# schematic.net
KiCad netlist of a schematic drawn in EAGLE
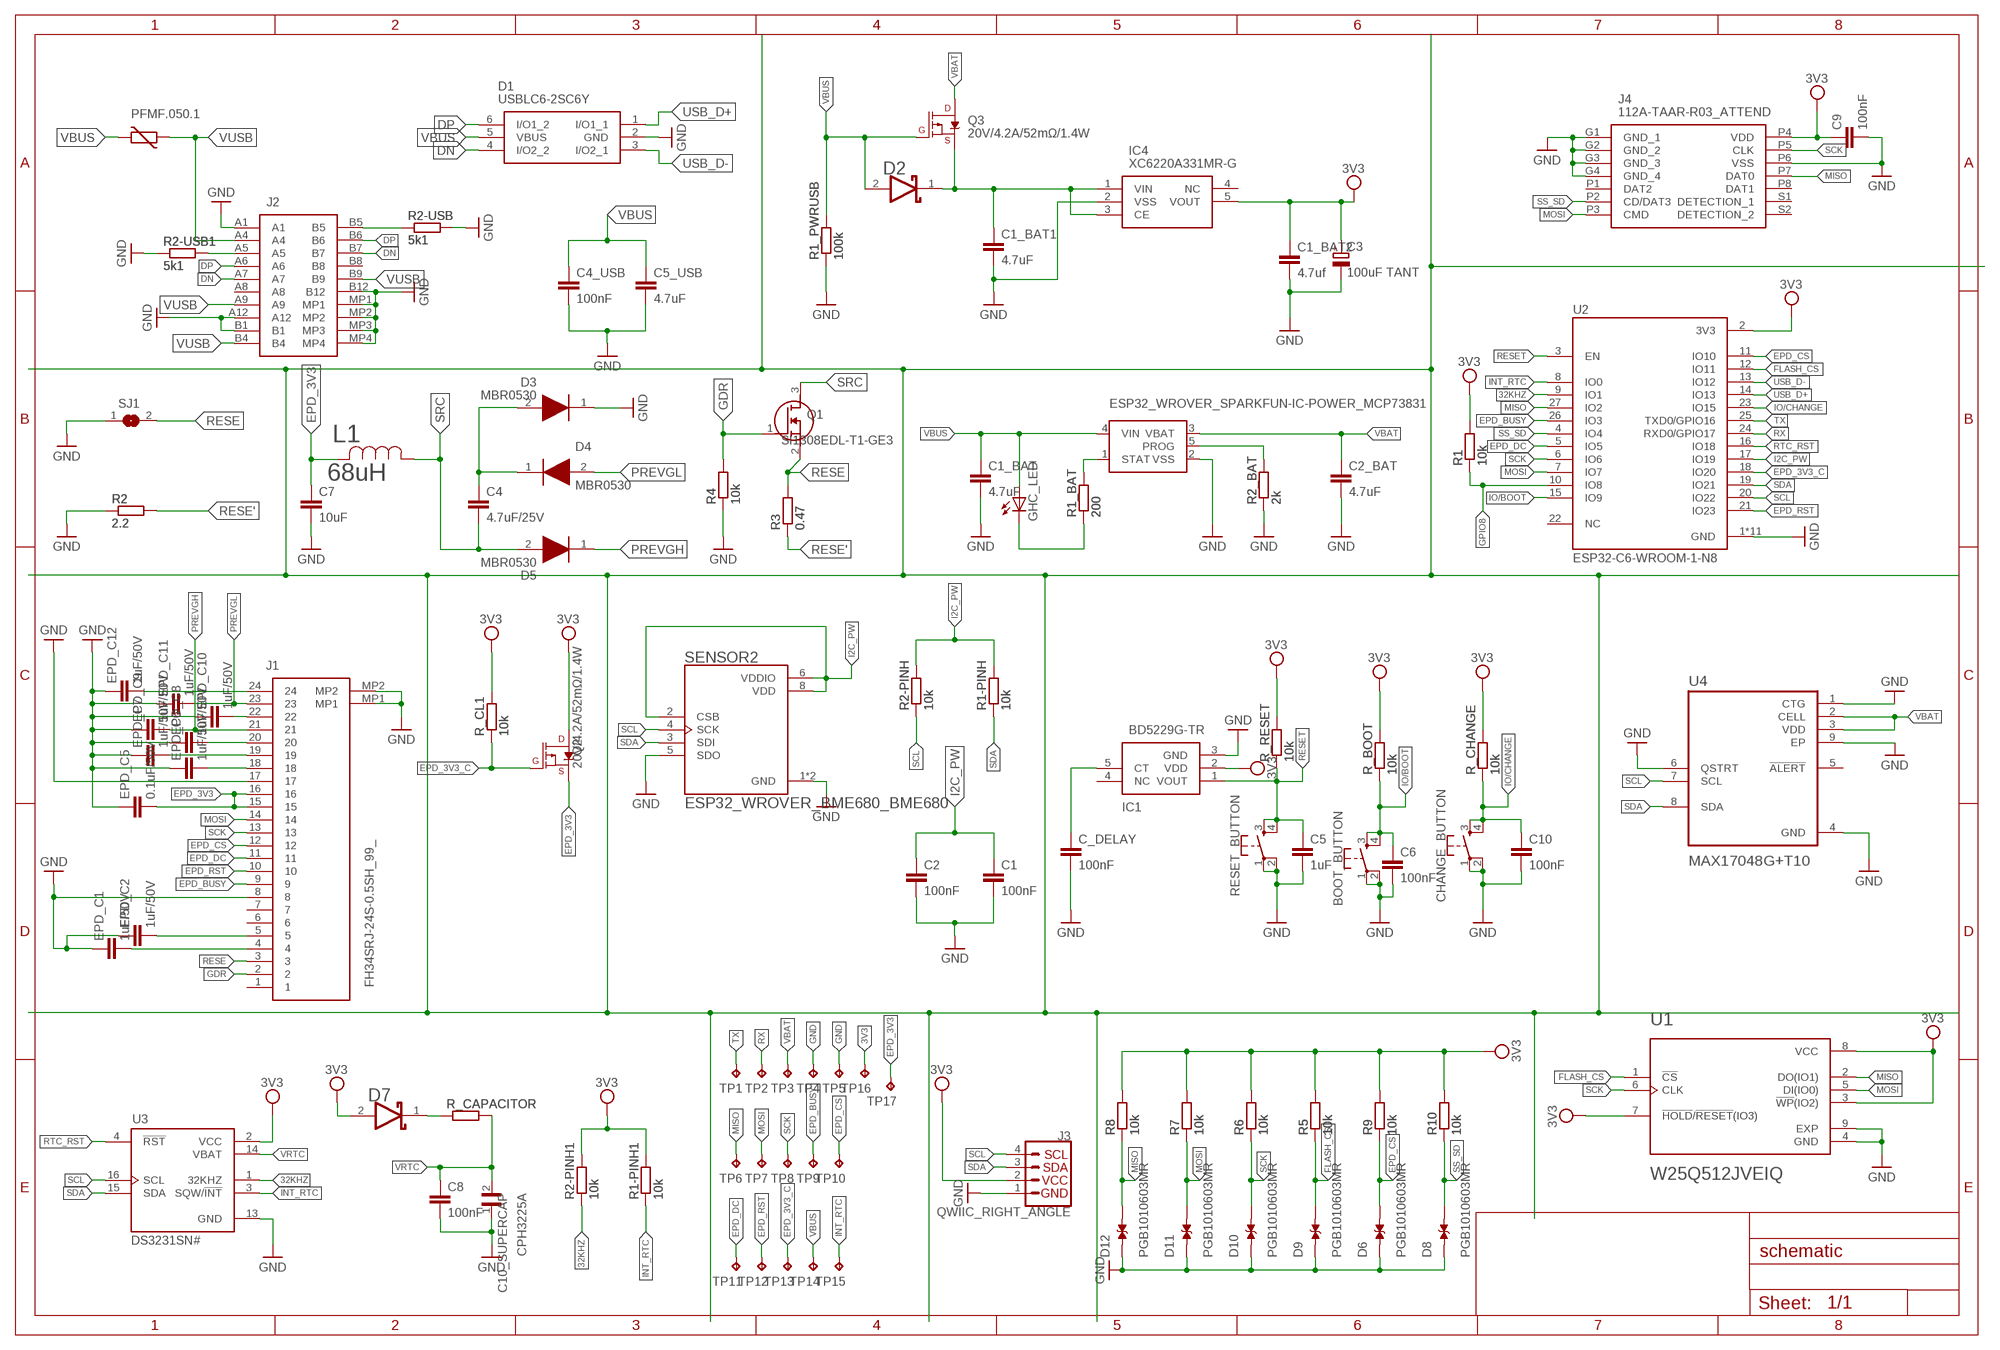
[diagram p0: schematic, sheet 1]

(export (version "E")
  (design (tool "Eeschema 10.0.6"))
  (components
    (comp (ref "BOOT_BUTTON")
      (value "BUTTON_CUSYOMV1")
      (footprint "eagle-import:MYBUTTON")
      (libsource (lib "eagle-import") (part "BUTTON_CUSYOMV1"))
    )
    (comp (ref "C1")
      (value "100nF")
      (footprint "eagle-import:ESP32_WROVER_EAGLE-LTSPICE_C0402")
      (libsource (lib "eagle-import") (part "ESP32_WROVER_EAGLE-LTSPICE_CC0402"))
    )
    (comp (ref "C1_BAT")
      (value "4.7uF")
      (footprint "eagle-import:EAGLE-LTSPICE_C0402")
      (libsource (lib "eagle-import") (part "EAGLE-LTSPICE_CC0402"))
    )
    (comp (ref "C1_BAT1")
      (value "4.7uF")
      (footprint "eagle-import:EAGLE-LTSPICE_C0402")
      (libsource (lib "eagle-import") (part "EAGLE-LTSPICE_CC0402"))
    )
    (comp (ref "C1_BAT2")
      (value "4.7uf")
      (footprint "eagle-import:EAGLE-LTSPICE_C0402")
      (libsource (lib "eagle-import") (part "EAGLE-LTSPICE_CC0402"))
    )
    (comp (ref "C2")
      (value "100nF")
      (footprint "eagle-import:ESP32_WROVER_EAGLE-LTSPICE_C0402")
      (libsource (lib "eagle-import") (part "ESP32_WROVER_EAGLE-LTSPICE_CC0402"))
    )
    (comp (ref "C2_BAT")
      (value "4.7uF")
      (footprint "eagle-import:EAGLE-LTSPICE_C0402")
      (libsource (lib "eagle-import") (part "EAGLE-LTSPICE_CC0402"))
    )
    (comp (ref "C3")
      (value "100uF TANT")
      (footprint "eagle-import:RCL_CT3528")
      (libsource (lib "eagle-import") (part "RCL_CPOL-EUCT3528"))
    )
    (comp (ref "C4")
      (value "4.7uF/25V")
      (footprint "eagle-import:ESP32_WROVER_EAGLE-LTSPICE_C0402")
      (libsource (lib "eagle-import") (part "ESP32_WROVER_EAGLE-LTSPICE_CC0402"))
    )
    (comp (ref "C4_USB")
      (value "100nF")
      (footprint "eagle-import:ESP32_WROVER_EAGLE-LTSPICE_C0402")
      (libsource (lib "eagle-import") (part "ESP32_WROVER_EAGLE-LTSPICE_CC0402"))
    )
    (comp (ref "C5")
      (value "1uF")
      (footprint "eagle-import:ESP32_WROVER_EAGLE-LTSPICE_C0402")
      (libsource (lib "eagle-import") (part "ESP32_WROVER_EAGLE-LTSPICE_CC0402"))
    )
    (comp (ref "C5_USB")
      (value "4.7uF")
      (footprint "eagle-import:ESP32_WROVER_EAGLE-LTSPICE_C0402")
      (libsource (lib "eagle-import") (part "ESP32_WROVER_EAGLE-LTSPICE_CC0402"))
    )
    (comp (ref "C6")
      (value "100nF")
      (footprint "eagle-import:ESP32_WROVER_EAGLE-LTSPICE_C0402")
      (libsource (lib "eagle-import") (part "ESP32_WROVER_EAGLE-LTSPICE_CC0402"))
    )
    (comp (ref "C7")
      (value "10uF")
      (footprint "eagle-import:ESP32_WROVER_EAGLE-LTSPICE_C0402")
      (libsource (lib "eagle-import") (part "ESP32_WROVER_EAGLE-LTSPICE_CC0402"))
    )
    (comp (ref "C8")
      (value "100nF")
      (footprint "eagle-import:ESP32_WROVER_EAGLE-LTSPICE_C0402")
      (libsource (lib "eagle-import") (part "ESP32_WROVER_EAGLE-LTSPICE_CC0402"))
    )
    (comp (ref "C9")
      (value "100nF")
      (footprint "eagle-import:ESP32_WROVER_EAGLE-LTSPICE_C0402")
      (libsource (lib "eagle-import") (part "ESP32_WROVER_EAGLE-LTSPICE_CC0402"))
    )
    (comp (ref "C10")
      (value "100nF")
      (footprint "eagle-import:ESP32_WROVER_EAGLE-LTSPICE_C0402")
      (libsource (lib "eagle-import") (part "ESP32_WROVER_EAGLE-LTSPICE_CC0402"))
    )
    (comp (ref "C10_SUPERCAP")
      (value "CPH3225A")
      (footprint "eagle-import:CAPCP3225X100N")
      (fields (field (name "MF") "Seiko Instruments"))
      (libsource (lib "eagle-import") (part "CPH3225A"))
    )
    (comp (ref "CHANGE_BUTTON")
      (value "BUTTON_CUSYOMV1")
      (footprint "eagle-import:MYBUTTON")
      (libsource (lib "eagle-import") (part "BUTTON_CUSYOMV1"))
    )
    (comp (ref "C_DELAY")
      (value "100nF")
      (footprint "eagle-import:ESP32_WROVER_EAGLE-LTSPICE_C0402")
      (libsource (lib "eagle-import") (part "ESP32_WROVER_EAGLE-LTSPICE_CC0402"))
    )
    (comp (ref "D1")
      (value "USBLC6-2SC6Y")
      (footprint "eagle-import:SOT95P280X145-6N")
      (fields (field (name "MF") "STMicroelectronics"))
      (libsource (lib "eagle-import") (part "USBLC6-2SC6Y"))
    )
    (comp (ref "D2")
      (value "ESP32_WROVER_AVX---SD0805S020S1R0_AVX_SD0805S020S1R0_0_0AVX_SD0805S020S1R0_0_0")
      (footprint "eagle-import:ESP32_WROVER_AVX---SD0805S020S1R0_AVX_SD0805S020S1R0_0")
      (fields
        (field (name "DIGIKEY_PART_NUMBER") "478-7800-1-ND")
        (field (name "MF") "AVX")
        (field (name "MOUSER_PART_NUMBER") "581-SD0805S020S1R0")
      )
      (libsource (lib "eagle-import") (part "ESP32_WROVER_AVX---SD0805S020S1R0_AVX_SD0805S020S1R0_0_0AVX_SD0805S020S1R0_0_0"))
    )
    (comp (ref "D3")
      (value "MBR0530")
      (footprint "eagle-import:SOD3716X135N")
      (fields (field (name "MF") "ON Semiconductor"))
      (libsource (lib "eagle-import") (part "MBR0530"))
    )
    (comp (ref "D4")
      (value "MBR0530")
      (footprint "eagle-import:SOD3716X135N")
      (fields (field (name "MF") "ON Semiconductor"))
      (libsource (lib "eagle-import") (part "MBR0530"))
    )
    (comp (ref "D5")
      (value "MBR0530")
      (footprint "eagle-import:SOD3716X135N")
      (fields (field (name "MF") "ON Semiconductor"))
      (libsource (lib "eagle-import") (part "MBR0530"))
    )
    (comp (ref "D6")
      (value "PGB1010603MR")
      (footprint "eagle-import:DIOC1608X36N")
      (fields (field (name "MF") "Littelfuse Inc."))
      (libsource (lib "eagle-import") (part "PGB1010603MR"))
    )
    (comp (ref "D7")
      (value "ESP32_WROVER_AVX---SD0805S020S1R0_AVX_SD0805S020S1R0_0_0AVX_SD0805S020S1R0_0_0")
      (footprint "eagle-import:ESP32_WROVER_AVX---SD0805S020S1R0_AVX_SD0805S020S1R0_0")
      (fields
        (field (name "DIGIKEY_PART_NUMBER") "478-7800-1-ND")
        (field (name "MF") "AVX")
        (field (name "MOUSER_PART_NUMBER") "581-SD0805S020S1R0")
      )
      (libsource (lib "eagle-import") (part "ESP32_WROVER_AVX---SD0805S020S1R0_AVX_SD0805S020S1R0_0_0AVX_SD0805S020S1R0_0_0"))
    )
    (comp (ref "D8")
      (value "PGB1010603MR")
      (footprint "eagle-import:DIOC1608X36N")
      (fields (field (name "MF") "Littelfuse Inc."))
      (libsource (lib "eagle-import") (part "PGB1010603MR"))
    )
    (comp (ref "D9")
      (value "PGB1010603MR")
      (footprint "eagle-import:DIOC1608X36N")
      (fields (field (name "MF") "Littelfuse Inc."))
      (libsource (lib "eagle-import") (part "PGB1010603MR"))
    )
    (comp (ref "D10")
      (value "PGB1010603MR")
      (footprint "eagle-import:DIOC1608X36N")
      (fields (field (name "MF") "Littelfuse Inc."))
      (libsource (lib "eagle-import") (part "PGB1010603MR"))
    )
    (comp (ref "D11")
      (value "PGB1010603MR")
      (footprint "eagle-import:DIOC1608X36N")
      (fields (field (name "MF") "Littelfuse Inc."))
      (libsource (lib "eagle-import") (part "PGB1010603MR"))
    )
    (comp (ref "D12")
      (value "PGB1010603MR")
      (footprint "eagle-import:DIOC1608X36N")
      (fields (field (name "MF") "Littelfuse Inc."))
      (libsource (lib "eagle-import") (part "PGB1010603MR"))
    )
    (comp (ref "EPD_C1")
      (value "1uF/50V")
      (footprint "eagle-import:ESP32_WROVER_EAGLE-LTSPICE_C0402")
      (libsource (lib "eagle-import") (part "ESP32_WROVER_EAGLE-LTSPICE_CC0402"))
    )
    (comp (ref "EPD_C2")
      (value "1uF/50V")
      (footprint "eagle-import:ESP32_WROVER_EAGLE-LTSPICE_C0402")
      (libsource (lib "eagle-import") (part "ESP32_WROVER_EAGLE-LTSPICE_CC0402"))
    )
    (comp (ref "EPD_C5")
      (value "0.1uF/50V")
      (footprint "eagle-import:ESP32_WROVER_EAGLE-LTSPICE_C0402")
      (libsource (lib "eagle-import") (part "ESP32_WROVER_EAGLE-LTSPICE_CC0402"))
    )
    (comp (ref "EPD_C6")
      (value "1uF/50V")
      (footprint "eagle-import:ESP32_WROVER_EAGLE-LTSPICE_C0402")
      (libsource (lib "eagle-import") (part "ESP32_WROVER_EAGLE-LTSPICE_CC0402"))
    )
    (comp (ref "EPD_C7")
      (value "1uF/50V")
      (footprint "eagle-import:ESP32_WROVER_EAGLE-LTSPICE_C0402")
      (libsource (lib "eagle-import") (part "ESP32_WROVER_EAGLE-LTSPICE_CC0402"))
    )
    (comp (ref "EPD_C8")
      (value "1uF/50V")
      (footprint "eagle-import:ESP32_WROVER_EAGLE-LTSPICE_C0402")
      (libsource (lib "eagle-import") (part "ESP32_WROVER_EAGLE-LTSPICE_CC0402"))
    )
    (comp (ref "EPD_C9")
      (value "1uF/50V")
      (footprint "eagle-import:ESP32_WROVER_EAGLE-LTSPICE_C0402")
      (libsource (lib "eagle-import") (part "ESP32_WROVER_EAGLE-LTSPICE_CC0402"))
    )
    (comp (ref "EPD_C10")
      (value "1uF/50V")
      (footprint "eagle-import:ESP32_WROVER_EAGLE-LTSPICE_C0402")
      (libsource (lib "eagle-import") (part "ESP32_WROVER_EAGLE-LTSPICE_CC0402"))
    )
    (comp (ref "EPD_C11")
      (value "1uF/50V")
      (footprint "eagle-import:ESP32_WROVER_EAGLE-LTSPICE_C0402")
      (libsource (lib "eagle-import") (part "ESP32_WROVER_EAGLE-LTSPICE_CC0402"))
    )
    (comp (ref "EPD_C12")
      (value "1uF/50V")
      (footprint "eagle-import:ESP32_WROVER_EAGLE-LTSPICE_C0402")
      (libsource (lib "eagle-import") (part "ESP32_WROVER_EAGLE-LTSPICE_CC0402"))
    )
    (comp (ref "GHC_LED")
      (value "ADAFRUIT_LEDCHIP-LED0603")
      (footprint "eagle-import:ADAFRUIT_CHIP-LED0603")
      (libsource (lib "eagle-import") (part "ADAFRUIT_LEDCHIP-LED0603"))
    )
    (comp (ref "IC1")
      (value "BD5229G-TR")
      (footprint "eagle-import:SOT95P280X125-5N")
      (fields (field (name "MOUSER_PART_NUMBER") "755-BD5229G-TR"))
      (libsource (lib "eagle-import") (part "BD5229G-TR"))
    )
    (comp (ref "IC4")
      (value "XC6220A331MR-G")
      (footprint "eagle-import:SOT95P280X120-5N")
      (fields (field (name "MOUSER_PART_NUMBER") "865-XC6220A331MR-G"))
      (libsource (lib "eagle-import") (part "XC6220A331MR-G"))
    )
    (comp (ref "J1")
      (value "FH34SRJ-24S-0.5SH_99_")
      (footprint "eagle-import:FH34SRJ24S05SH99")
      (fields
        (field (name "MANUFACTURER_PART_NUMBER") "FH34SRJ-24S-0.5SH(99)")
        (field (name "MOUSER_PART_NUMBER") "798-FH34SRJ24S05SH99")
      )
      (libsource (lib "eagle-import") (part "FH34SRJ-24S-0.5SH_99_"))
    )
    (comp (ref "J2")
      (value "SAMACSYS_PARTS_USB4110-GF-A")
      (footprint "eagle-import:SAMACSYS_PARTS_USB4110GFA")
      (fields
        (field (name "MANUFACTURER_PART_NUMBER") "USB4110-GF-A")
        (field (name "MOUSER_PART_NUMBER") "640-USB4110-GF-A")
      )
      (libsource (lib "eagle-import") (part "SAMACSYS_PARTS_USB4110-GF-A"))
    )
    (comp (ref "J3")
      (value "QWIIC_RIGHT_ANGLE")
      (footprint "eagle-import:JST04_1MM_RA")
      (libsource (lib "eagle-import") (part "QWIIC_CONNECTORJS-1MM"))
    )
    (comp (ref "J4")
      (value "112A-TAAR-R03_ATTEND")
      (footprint "eagle-import:112ATAARR03ATTEND")
      (fields (field (name "MANUFACTURER_PART_NUMBER") "112A-TAAR-R03 ATTEND"))
      (libsource (lib "eagle-import") (part "112A-TAAR-R03_ATTEND"))
    )
    (comp (ref "L1")
      (value "68uH")
      (footprint "eagle-import:IND_4828-WE-TPC_WRE")
      (fields
        (field (name "MANUFACTURER_PART_NUMBER") "744043680")
        (field (name "COPYRIGHT") "Copyright (C) 2024 Ultra Librarian. All rights reserved.")
      )
      (libsource (lib "eagle-import") (part "744043680IND_4828-WE-TPC_WRE"))
    )
    (comp (ref "PFMF.050.1")
      (value "ESP32C6_VARISTORCN1812")
      (footprint "eagle-import:ESP32C6_VARISTOR_CT_CN1812")
      (libsource (lib "eagle-import") (part "ESP32C6_VARISTORCN1812"))
    )
    (comp (ref "Q1")
      (value "SI1308EDL-T1-GE3")
      (footprint "eagle-import:SOT65P210X110-3N")
      (fields (field (name "MF") "Vishay Siliconix"))
      (libsource (lib "eagle-import") (part "SI1308EDL-T1-GE3"))
    )
    (comp (ref "Q2")
      (value "20V/4.2A/52mΩ/1.4W")
      (footprint "eagle-import:ESP32_WROVER_SPARKFUN-DISCRETESEMI_SOT23-3")
      (libsource (lib "eagle-import") (part "ESP32_WROVER_SPARKFUN-DISCRETESEMI_MOSFET_PCH-DMG2305UX-7"))
    )
    (comp (ref "Q3")
      (value "20V/4.2A/52mΩ/1.4W")
      (footprint "eagle-import:ESP32_WROVER_SPARKFUN-DISCRETESEMI_SOT23-3")
      (libsource (lib "eagle-import") (part "ESP32_WROVER_SPARKFUN-DISCRETESEMI_MOSFET_PCH-DMG2305UX-7"))
    )
    (comp (ref "R1")
      (value "10k")
      (footprint "eagle-import:ESP32_WROVER_EAGLE-LTSPICE_R0402")
      (libsource (lib "eagle-import") (part "ESP32_WROVER_EAGLE-LTSPICE_RR0402"))
    )
    (comp (ref "R1-PINH")
      (value "10k")
      (footprint "eagle-import:ESP32_WROVER_EAGLE-LTSPICE_R0402")
      (libsource (lib "eagle-import") (part "ESP32_WROVER_EAGLE-LTSPICE_RR0402"))
    )
    (comp (ref "R1-PINH1")
      (value "10k")
      (footprint "eagle-import:ESP32_WROVER_EAGLE-LTSPICE_R0402")
      (libsource (lib "eagle-import") (part "ESP32_WROVER_EAGLE-LTSPICE_RR0402"))
    )
    (comp (ref "R1_BAT")
      (value "200")
      (footprint "eagle-import:ESP32_WROVER_EAGLE-LTSPICE_R0402")
      (libsource (lib "eagle-import") (part "ESP32_WROVER_EAGLE-LTSPICE_RR0402"))
    )
    (comp (ref "R1_PWRUSB")
      (value "100k")
      (footprint "eagle-import:ESP32_WROVER_EAGLE-LTSPICE_R0402")
      (libsource (lib "eagle-import") (part "ESP32_WROVER_EAGLE-LTSPICE_RR0402"))
    )
    (comp (ref "R2")
      (value "2.2")
      (footprint "eagle-import:ESP32_WROVER_EAGLE-LTSPICE_R0402")
      (libsource (lib "eagle-import") (part "ESP32_WROVER_EAGLE-LTSPICE_RR0402"))
    )
    (comp (ref "R2-PINH")
      (value "10k")
      (footprint "eagle-import:ESP32_WROVER_EAGLE-LTSPICE_R0402")
      (libsource (lib "eagle-import") (part "ESP32_WROVER_EAGLE-LTSPICE_RR0402"))
    )
    (comp (ref "R2-PINH1")
      (value "10k")
      (footprint "eagle-import:ESP32_WROVER_EAGLE-LTSPICE_R0402")
      (libsource (lib "eagle-import") (part "ESP32_WROVER_EAGLE-LTSPICE_RR0402"))
    )
    (comp (ref "R2-USB")
      (value "5k1")
      (footprint "eagle-import:ESP32_WROVER_EAGLE-LTSPICE_R0402")
      (libsource (lib "eagle-import") (part "ESP32_WROVER_EAGLE-LTSPICE_RR0402"))
    )
    (comp (ref "R2-USB1")
      (value "5k1")
      (footprint "eagle-import:ESP32_WROVER_EAGLE-LTSPICE_R0402")
      (libsource (lib "eagle-import") (part "ESP32_WROVER_EAGLE-LTSPICE_RR0402"))
    )
    (comp (ref "R2_BAT")
      (value "2k")
      (footprint "eagle-import:ESP32_WROVER_EAGLE-LTSPICE_R0402")
      (libsource (lib "eagle-import") (part "ESP32_WROVER_EAGLE-LTSPICE_RR0402"))
    )
    (comp (ref "R3")
      (value "0.47")
      (footprint "eagle-import:ESP32_WROVER_EAGLE-LTSPICE_R0402")
      (libsource (lib "eagle-import") (part "ESP32_WROVER_EAGLE-LTSPICE_RR0402"))
    )
    (comp (ref "R4")
      (value "10k")
      (footprint "eagle-import:ESP32_WROVER_EAGLE-LTSPICE_R0402")
      (libsource (lib "eagle-import") (part "ESP32_WROVER_EAGLE-LTSPICE_RR0402"))
    )
    (comp (ref "R5")
      (value "10k")
      (footprint "eagle-import:ESP32_WROVER_EAGLE-LTSPICE_R0402")
      (libsource (lib "eagle-import") (part "ESP32_WROVER_EAGLE-LTSPICE_RR0402"))
    )
    (comp (ref "R6")
      (value "10k")
      (footprint "eagle-import:ESP32_WROVER_EAGLE-LTSPICE_R0402")
      (libsource (lib "eagle-import") (part "ESP32_WROVER_EAGLE-LTSPICE_RR0402"))
    )
    (comp (ref "R7")
      (value "10k")
      (footprint "eagle-import:ESP32_WROVER_EAGLE-LTSPICE_R0402")
      (libsource (lib "eagle-import") (part "ESP32_WROVER_EAGLE-LTSPICE_RR0402"))
    )
    (comp (ref "R8")
      (value "10k")
      (footprint "eagle-import:ESP32_WROVER_EAGLE-LTSPICE_R0402")
      (libsource (lib "eagle-import") (part "ESP32_WROVER_EAGLE-LTSPICE_RR0402"))
    )
    (comp (ref "R9")
      (value "10k")
      (footprint "eagle-import:ESP32_WROVER_EAGLE-LTSPICE_R0402")
      (libsource (lib "eagle-import") (part "ESP32_WROVER_EAGLE-LTSPICE_RR0402"))
    )
    (comp (ref "R10")
      (value "10k")
      (footprint "eagle-import:ESP32_WROVER_EAGLE-LTSPICE_R0402")
      (libsource (lib "eagle-import") (part "ESP32_WROVER_EAGLE-LTSPICE_RR0402"))
    )
    (comp (ref "RESET_BUTTON")
      (value "BUTTON_CUSYOMV1")
      (footprint "eagle-import:MYBUTTON")
      (libsource (lib "eagle-import") (part "BUTTON_CUSYOMV1"))
    )
    (comp (ref "R_BOOT")
      (value "10k")
      (footprint "eagle-import:ESP32_WROVER_EAGLE-LTSPICE_R0402")
      (libsource (lib "eagle-import") (part "ESP32_WROVER_EAGLE-LTSPICE_RR0402"))
    )
    (comp (ref "R_CAPACITOR")
      (value "ESP32_WROVER_EAGLE-LTSPICE_RR0402")
      (footprint "eagle-import:ESP32_WROVER_EAGLE-LTSPICE_R0402")
      (libsource (lib "eagle-import") (part "ESP32_WROVER_EAGLE-LTSPICE_RR0402"))
    )
    (comp (ref "R_CHANGE")
      (value "10k")
      (footprint "eagle-import:ESP32_WROVER_EAGLE-LTSPICE_R0402")
      (libsource (lib "eagle-import") (part "ESP32_WROVER_EAGLE-LTSPICE_RR0402"))
    )
    (comp (ref "R_CL1")
      (value "10k")
      (footprint "eagle-import:ESP32_WROVER_EAGLE-LTSPICE_R0402")
      (libsource (lib "eagle-import") (part "ESP32_WROVER_EAGLE-LTSPICE_RR0402"))
    )
    (comp (ref "R_RESET")
      (value "10k")
      (footprint "eagle-import:ESP32_WROVER_EAGLE-LTSPICE_R0402")
      (libsource (lib "eagle-import") (part "ESP32_WROVER_EAGLE-LTSPICE_RR0402"))
    )
    (comp (ref "SENSOR2")
      (value "ESP32_WROVER_BME680_BME680")
      (footprint "eagle-import:ESP32_WROVER_BME680_PSON80P300X300X100-8N")
      (fields (field (name "MF") "Bosch Sensortec") (field (name "MP") "BME680"))
      (libsource (lib "eagle-import") (part "ESP32_WROVER_BME680_BME680"))
    )
    (comp (ref "SJ1") (value "SJ") (footprint "eagle-import:SJ") (libsource (lib "eagle-import") (part "SJ")))
    (comp (ref "TP1")
      (value "TPTP20R")
      (footprint "eagle-import:TP20R")
      (libsource (lib "eagle-import") (part "TPTP20R"))
    )
    (comp (ref "TP2")
      (value "TPTP20R")
      (footprint "eagle-import:TP20R")
      (libsource (lib "eagle-import") (part "TPTP20R"))
    )
    (comp (ref "TP3")
      (value "TPTP20R")
      (footprint "eagle-import:TP20R")
      (libsource (lib "eagle-import") (part "TPTP20R"))
    )
    (comp (ref "TP4")
      (value "TPTP20R")
      (footprint "eagle-import:TP20R")
      (libsource (lib "eagle-import") (part "TPTP20R"))
    )
    (comp (ref "TP5")
      (value "TPTP20R")
      (footprint "eagle-import:TP20R")
      (libsource (lib "eagle-import") (part "TPTP20R"))
    )
    (comp (ref "TP6")
      (value "TPTP20R")
      (footprint "eagle-import:TP20R")
      (libsource (lib "eagle-import") (part "TPTP20R"))
    )
    (comp (ref "TP7")
      (value "TPTP20R")
      (footprint "eagle-import:TP20R")
      (libsource (lib "eagle-import") (part "TPTP20R"))
    )
    (comp (ref "TP8")
      (value "TPTP20R")
      (footprint "eagle-import:TP20R")
      (libsource (lib "eagle-import") (part "TPTP20R"))
    )
    (comp (ref "TP9")
      (value "TPTP20R")
      (footprint "eagle-import:TP20R")
      (libsource (lib "eagle-import") (part "TPTP20R"))
    )
    (comp (ref "TP10")
      (value "TPTP20R")
      (footprint "eagle-import:TP20R")
      (libsource (lib "eagle-import") (part "TPTP20R"))
    )
    (comp (ref "TP11")
      (value "TPTP20R")
      (footprint "eagle-import:TP20R")
      (libsource (lib "eagle-import") (part "TPTP20R"))
    )
    (comp (ref "TP12")
      (value "TPTP20R")
      (footprint "eagle-import:TP20R")
      (libsource (lib "eagle-import") (part "TPTP20R"))
    )
    (comp (ref "TP13")
      (value "TPTP20R")
      (footprint "eagle-import:TP20R")
      (libsource (lib "eagle-import") (part "TPTP20R"))
    )
    (comp (ref "TP14")
      (value "TPTP20R")
      (footprint "eagle-import:TP20R")
      (libsource (lib "eagle-import") (part "TPTP20R"))
    )
    (comp (ref "TP15")
      (value "TPTP20R")
      (footprint "eagle-import:TP20R")
      (libsource (lib "eagle-import") (part "TPTP20R"))
    )
    (comp (ref "TP16")
      (value "TPTP20R")
      (footprint "eagle-import:TP20R")
      (libsource (lib "eagle-import") (part "TPTP20R"))
    )
    (comp (ref "TP17")
      (value "TPTP20R")
      (footprint "eagle-import:TP20R")
      (libsource (lib "eagle-import") (part "TPTP20R"))
    )
    (comp (ref "U")
      (value "ESP32_WROVER_SPARKFUN-IC-POWER_MCP73831")
      (footprint "eagle-import:ESP32_WROVER_SPARKFUN-IC-POWER_SOT23-5")
      (libsource (lib "eagle-import") (part "ESP32_WROVER_SPARKFUN-IC-POWER_MCP73831"))
    )
    (comp (ref "U1")
      (value "W25Q512JVEIQ")
      (footprint "eagle-import:SON127P600X800X80-9N")
      (fields (field (name "MF") "Winbond Electronics"))
      (libsource (lib "eagle-import") (part "W25Q512JVEIQ"))
    )
    (comp (ref "U2")
      (value "ESP32-C6-WROOM-1-N8")
      (footprint "eagle-import:XCVR_ESP32-C6-WROOM-1-N8")
      (fields (field (name "MF") "Espressif Systems"))
      (libsource (lib "eagle-import") (part "ESP32-C6-WROOM-1-N8"))
    )
    (comp (ref "U3")
      (value "DS3231SN#")
      (footprint "eagle-import:SOIC127P1032X265-16N")
      (fields (field (name "MF") "Analog Devices"))
      (libsource (lib "eagle-import") (part "DS3231SN#"))
    )
    (comp (ref "U4")
      (value "MAX17048G+T10")
      (footprint "eagle-import:SON50P200X200X80-9N")
      (fields (field (name "MF") "Analog Devices"))
      (libsource (lib "eagle-import") (part "MAX17048G+T10"))
    )
  )
  (nets
    (net (code "1") (name "3V3") (class "Default")
      (node (ref "C1_BAT2") (pin "1") (pinfunction "1_1") (pintype "passive"))
      (node (ref "C3") (pin "+") (pinfunction "+_+") (pintype "passive"))
      (node (ref "C9") (pin "1") (pinfunction "1_1") (pintype "passive"))
      (node (ref "D7") (pin "2") (pinfunction "ANODE_2") (pintype "bidirectional"))
      (node (ref "IC1") (pin "2") (pinfunction "VDD_2") (pintype "bidirectional"))
      (node (ref "IC4") (pin "5") (pinfunction "VOUT_5") (pintype "bidirectional"))
      (node (ref "J3") (pin "2") (pinfunction "2_2") (pintype "power_in"))
      (node (ref "J4") (pin "P4") (pinfunction "VDD_P4") (pintype "bidirectional"))
      (node (ref "Q2") (pin "3") (pinfunction "D_3") (pintype "bidirectional"))
      (node (ref "R1") (pin "2") (pinfunction "2_2") (pintype "passive"))
      (node (ref "R1-PINH1") (pin "2") (pinfunction "2_2") (pintype "passive"))
      (node (ref "R10") (pin "2") (pinfunction "2_2") (pintype "passive"))
      (node (ref "R2-PINH1") (pin "2") (pinfunction "2_2") (pintype "passive"))
      (node (ref "R5") (pin "2") (pinfunction "2_2") (pintype "passive"))
      (node (ref "R6") (pin "2") (pinfunction "2_2") (pintype "passive"))
      (node (ref "R7") (pin "2") (pinfunction "2_2") (pintype "passive"))
      (node (ref "R8") (pin "2") (pinfunction "2_2") (pintype "passive"))
      (node (ref "R9") (pin "2") (pinfunction "2_2") (pintype "passive"))
      (node (ref "R_BOOT") (pin "2") (pinfunction "2_2") (pintype "passive"))
      (node (ref "R_CHANGE") (pin "2") (pinfunction "2_2") (pintype "passive"))
      (node (ref "R_CL1") (pin "2") (pinfunction "2_2") (pintype "passive"))
      (node (ref "R_RESET") (pin "2") (pinfunction "2_2") (pintype "passive"))
      (node (ref "TP16") (pin "TP") (pinfunction "TP_TP") (pintype "input"))
      (node (ref "U1") (pin "3") (pinfunction "~{WP}(IO2)_3") (pintype "bidirectional"))
      (node (ref "U1") (pin "7") (pinfunction "~{HOLD}/~{RESET}(IO3)_7") (pintype "bidirectional"))
      (node (ref "U1") (pin "8") (pinfunction "VCC_8") (pintype "power_in"))
      (node (ref "U2") (pin "2") (pinfunction "3V3_2") (pintype "power_in"))
      (node (ref "U3") (pin "2") (pinfunction "VCC_2") (pintype "power_in"))
    )
    (net (code "2") (name "32KHZ") (class "Default")
      (node (ref "R2-PINH1") (pin "1") (pinfunction "1_1") (pintype "passive"))
      (node (ref "U2") (pin "9") (pinfunction "IO1_9") (pintype "bidirectional"))
      (node (ref "U3") (pin "1") (pinfunction "32KHZ_1") (pintype "output"))
    )
    (net (code "3") (name "DN") (class "Default")
      (node (ref "D1") (pin "4") (pinfunction "I/O2_2_4") (pintype "bidirectional"))
      (node (ref "J2") (pin "A7") (pinfunction "A7_A7") (pintype "bidirectional"))
      (node (ref "J2") (pin "B7") (pinfunction "B7_B7") (pintype "bidirectional"))
    )
    (net (code "4") (name "DP") (class "Default")
      (node (ref "D1") (pin "6") (pinfunction "I/O1_2_6") (pintype "bidirectional"))
      (node (ref "J2") (pin "A6") (pinfunction "A6_A6") (pintype "bidirectional"))
      (node (ref "J2") (pin "B6") (pinfunction "B6_B6") (pintype "bidirectional"))
    )
    (net (code "5") (name "EPD_3V3") (class "Default")
      (node (ref "C7") (pin "1") (pinfunction "1_1") (pintype "passive"))
      (node (ref "EPD_C5") (pin "2") (pinfunction "2_2") (pintype "passive"))
      (node (ref "J1") (pin "15") (pinfunction "15_15") (pintype "bidirectional"))
      (node (ref "J1") (pin "16") (pinfunction "16_16") (pintype "bidirectional"))
      (node (ref "L1") (pin "2") (pinfunction "2_2") (pintype "passive"))
      (node (ref "Q2") (pin "2") (pinfunction "S_2") (pintype "bidirectional"))
      (node (ref "TP17") (pin "TP") (pinfunction "TP_TP") (pintype "input"))
    )
    (net (code "6") (name "EPD_3V3_C") (class "Default")
      (node (ref "Q2") (pin "1") (pinfunction "G_1") (pintype "bidirectional"))
      (node (ref "R_CL1") (pin "1") (pinfunction "1_1") (pintype "passive"))
      (node (ref "TP13") (pin "TP") (pinfunction "TP_TP") (pintype "input"))
      (node (ref "U2") (pin "18") (pinfunction "IO20_18") (pintype "bidirectional"))
    )
    (net (code "7") (name "EPD_BUSY") (class "Default")
      (node (ref "J1") (pin "9") (pinfunction "9_9") (pintype "bidirectional"))
      (node (ref "TP9") (pin "TP") (pinfunction "TP_TP") (pintype "input"))
      (node (ref "U2") (pin "26") (pinfunction "IO3_26") (pintype "bidirectional"))
    )
    (net (code "8") (name "EPD_CS") (class "Default")
      (node (ref "D6") (pin "2") (pinfunction "2_2") (pintype "passive"))
      (node (ref "J1") (pin "12") (pinfunction "12_12") (pintype "bidirectional"))
      (node (ref "R9") (pin "1") (pinfunction "1_1") (pintype "passive"))
      (node (ref "TP10") (pin "TP") (pinfunction "TP_TP") (pintype "input"))
      (node (ref "U2") (pin "11") (pinfunction "IO10_11") (pintype "bidirectional"))
    )
    (net (code "9") (name "EPD_DC") (class "Default")
      (node (ref "J1") (pin "11") (pinfunction "11_11") (pintype "bidirectional"))
      (node (ref "TP11") (pin "TP") (pinfunction "TP_TP") (pintype "input"))
      (node (ref "U2") (pin "5") (pinfunction "IO5_5") (pintype "bidirectional"))
    )
    (net (code "10") (name "EPD_RST") (class "Default")
      (node (ref "J1") (pin "10") (pinfunction "10_10") (pintype "bidirectional"))
      (node (ref "TP12") (pin "TP") (pinfunction "TP_TP") (pintype "input"))
      (node (ref "U2") (pin "21") (pinfunction "IO23_21") (pintype "bidirectional"))
    )
    (net (code "11") (name "FLASH_CS") (class "Default")
      (node (ref "D9") (pin "2") (pinfunction "2_2") (pintype "passive"))
      (node (ref "R5") (pin "1") (pinfunction "1_1") (pintype "passive"))
      (node (ref "U1") (pin "1") (pinfunction "~{CS}_1") (pintype "input"))
      (node (ref "U2") (pin "12") (pinfunction "IO11_12") (pintype "bidirectional"))
    )
    (net (code "12") (name "GDR") (class "Default")
      (node (ref "J1") (pin "2") (pinfunction "2_2") (pintype "bidirectional"))
      (node (ref "Q1") (pin "1") (pinfunction "G_1") (pintype "bidirectional"))
      (node (ref "R4") (pin "2") (pinfunction "2_2") (pintype "passive"))
    )
    (net (code "13") (name "GND") (class "Default")
      (node (ref "BOOT_BUTTON") (pin "1") (pinfunction "1_1") (pintype "passive"))
      (node (ref "BOOT_BUTTON") (pin "2") (pinfunction "2_2") (pintype "passive"))
      (node (ref "C1") (pin "2") (pinfunction "2_2") (pintype "passive"))
      (node (ref "C10") (pin "2") (pinfunction "2_2") (pintype "passive"))
      (node (ref "C10_SUPERCAP") (pin "1") (pinfunction "1_1") (pintype "passive"))
      (node (ref "C1_BAT") (pin "2") (pinfunction "2_2") (pintype "passive"))
      (node (ref "C1_BAT1") (pin "2") (pinfunction "2_2") (pintype "passive"))
      (node (ref "C1_BAT2") (pin "2") (pinfunction "2_2") (pintype "passive"))
      (node (ref "C2") (pin "2") (pinfunction "2_2") (pintype "passive"))
      (node (ref "C2_BAT") (pin "2") (pinfunction "2_2") (pintype "passive"))
      (node (ref "C3") (pin "-") (pinfunction "-_-") (pintype "passive"))
      (node (ref "C4_USB") (pin "2") (pinfunction "2_2") (pintype "passive"))
      (node (ref "C5") (pin "2") (pinfunction "2_2") (pintype "passive"))
      (node (ref "C5_USB") (pin "2") (pinfunction "2_2") (pintype "passive"))
      (node (ref "C6") (pin "2") (pinfunction "2_2") (pintype "passive"))
      (node (ref "C7") (pin "2") (pinfunction "2_2") (pintype "passive"))
      (node (ref "C8") (pin "2") (pinfunction "2_2") (pintype "passive"))
      (node (ref "C9") (pin "2") (pinfunction "2_2") (pintype "passive"))
      (node (ref "CHANGE_BUTTON") (pin "1") (pinfunction "1_1") (pintype "passive"))
      (node (ref "CHANGE_BUTTON") (pin "2") (pinfunction "2_2") (pintype "passive"))
      (node (ref "C_DELAY") (pin "2") (pinfunction "2_2") (pintype "passive"))
      (node (ref "D1") (pin "2") (pinfunction "GND_2") (pintype "bidirectional"))
      (node (ref "D10") (pin "1") (pinfunction "1_1") (pintype "passive"))
      (node (ref "D11") (pin "1") (pinfunction "1_1") (pintype "passive"))
      (node (ref "D12") (pin "1") (pinfunction "1_1") (pintype "passive"))
      (node (ref "D3") (pin "1") (pinfunction "K_1") (pintype "bidirectional"))
      (node (ref "D6") (pin "1") (pinfunction "1_1") (pintype "passive"))
      (node (ref "D8") (pin "1") (pinfunction "1_1") (pintype "passive"))
      (node (ref "D9") (pin "1") (pinfunction "1_1") (pintype "passive"))
      (node (ref "EPD_C1") (pin "1") (pinfunction "1_1") (pintype "passive"))
      (node (ref "EPD_C10") (pin "1") (pinfunction "1_1") (pintype "passive"))
      (node (ref "EPD_C11") (pin "1") (pinfunction "1_1") (pintype "passive"))
      (node (ref "EPD_C12") (pin "1") (pinfunction "1_1") (pintype "passive"))
      (node (ref "EPD_C2") (pin "1") (pinfunction "1_1") (pintype "passive"))
      (node (ref "EPD_C5") (pin "1") (pinfunction "1_1") (pintype "passive"))
      (node (ref "EPD_C6") (pin "1") (pinfunction "1_1") (pintype "passive"))
      (node (ref "EPD_C7") (pin "1") (pinfunction "1_1") (pintype "passive"))
      (node (ref "EPD_C8") (pin "1") (pinfunction "1_1") (pintype "passive"))
      (node (ref "EPD_C9") (pin "1") (pinfunction "1_1") (pintype "passive"))
      (node (ref "IC1") (pin "3") (pinfunction "GND_3") (pintype "bidirectional"))
      (node (ref "IC4") (pin "2") (pinfunction "VSS_2") (pintype "bidirectional"))
      (node (ref "J1") (pin "17") (pinfunction "17_17") (pintype "bidirectional"))
      (node (ref "J1") (pin "8") (pinfunction "8_8") (pintype "bidirectional"))
      (node (ref "J1") (pin "MP1") (pinfunction "MP1_MP1") (pintype "bidirectional"))
      (node (ref "J1") (pin "MP2") (pinfunction "MP2_MP2") (pintype "bidirectional"))
      (node (ref "J2") (pin "A1") (pinfunction "A1_A1") (pintype "bidirectional"))
      (node (ref "J2") (pin "A12") (pinfunction "A12_A12") (pintype "bidirectional"))
      (node (ref "J2") (pin "B1") (pinfunction "B1_B1") (pintype "bidirectional"))
      (node (ref "J2") (pin "B12") (pinfunction "B12_B12") (pintype "bidirectional"))
      (node (ref "J2") (pin "MP1") (pinfunction "MP1_MP1") (pintype "bidirectional"))
      (node (ref "J2") (pin "MP2") (pinfunction "MP2_MP2") (pintype "bidirectional"))
      (node (ref "J2") (pin "MP3") (pinfunction "MP3_MP3") (pintype "bidirectional"))
      (node (ref "J2") (pin "MP4") (pinfunction "MP4_MP4") (pintype "bidirectional"))
      (node (ref "J3") (pin "1") (pinfunction "1_1") (pintype "power_in"))
      (node (ref "J4") (pin "G1") (pinfunction "GND_1_G1") (pintype "bidirectional"))
      (node (ref "J4") (pin "G2") (pinfunction "GND_2_G2") (pintype "bidirectional"))
      (node (ref "J4") (pin "G3") (pinfunction "GND_3_G3") (pintype "bidirectional"))
      (node (ref "J4") (pin "G4") (pinfunction "GND_4_G4") (pintype "bidirectional"))
      (node (ref "J4") (pin "P6") (pinfunction "VSS_P6") (pintype "bidirectional"))
      (node (ref "R1_PWRUSB") (pin "1") (pinfunction "1_1") (pintype "passive"))
      (node (ref "R2") (pin "1") (pinfunction "1_1") (pintype "passive"))
      (node (ref "R2-USB") (pin "2") (pinfunction "2_2") (pintype "passive"))
      (node (ref "R2-USB1") (pin "1") (pinfunction "1_1") (pintype "passive"))
      (node (ref "R2_BAT") (pin "1") (pinfunction "1_1") (pintype "passive"))
      (node (ref "R4") (pin "1") (pinfunction "1_1") (pintype "passive"))
      (node (ref "RESET_BUTTON") (pin "1") (pinfunction "1_1") (pintype "passive"))
      (node (ref "RESET_BUTTON") (pin "2") (pinfunction "2_2") (pintype "passive"))
      (node (ref "SENSOR2") (pin "1") (pinfunction "GND_1") (pintype "power_in"))
      (node (ref "SENSOR2") (pin "5") (pinfunction "SDO_5") (pintype "bidirectional"))
      (node (ref "SENSOR2") (pin "7") (pinfunction "GND_7") (pintype "power_in"))
      (node (ref "SJ1") (pin "1") (pinfunction "1_1") (pintype "passive"))
      (node (ref "TP4") (pin "TP") (pinfunction "TP_TP") (pintype "input"))
      (node (ref "TP5") (pin "TP") (pinfunction "TP_TP") (pintype "input"))
      (node (ref "U") (pin "2") (pinfunction "VSS_2") (pintype "power_in"))
      (node (ref "U1") (pin "4") (pinfunction "GND_4") (pintype "power_in"))
      (node (ref "U1") (pin "9") (pinfunction "EXP_9") (pintype "passive"))
      (node (ref "U2") (pin "1") (pinfunction "GND_1") (pintype "power_in"))
      (node (ref "U2") (pin "28") (pinfunction "GND_28") (pintype "power_in"))
      (node (ref "U2") (pin "29_1") (pinfunction "GND_29_1") (pintype "power_in"))
      (node (ref "U2") (pin "29_2") (pinfunction "GND_29_2") (pintype "power_in"))
      (node (ref "U2") (pin "29_3") (pinfunction "GND_29_3") (pintype "power_in"))
      (node (ref "U2") (pin "29_4") (pinfunction "GND_29_4") (pintype "power_in"))
      (node (ref "U2") (pin "29_5") (pinfunction "GND_29_5") (pintype "power_in"))
      (node (ref "U2") (pin "29_6") (pinfunction "GND_29_6") (pintype "power_in"))
      (node (ref "U2") (pin "29_7") (pinfunction "GND_29_7") (pintype "power_in"))
      (node (ref "U2") (pin "29_8") (pinfunction "GND_29_8") (pintype "power_in"))
      (node (ref "U2") (pin "29_9") (pinfunction "GND_29_9") (pintype "power_in"))
      (node (ref "U3") (pin "13") (pinfunction "GND_13") (pintype "power_in"))
      (node (ref "U4") (pin "1") (pinfunction "CTG_1") (pintype "power_in"))
      (node (ref "U4") (pin "4") (pinfunction "GND_4") (pintype "power_in"))
      (node (ref "U4") (pin "6") (pinfunction "QSTRT_6") (pintype "input"))
      (node (ref "U4") (pin "9") (pinfunction "EP_9") (pintype "power_in"))
    )
    (net (code "14") (name "GPIO8") (class "Default")
      (node (ref "R1") (pin "1") (pinfunction "1_1") (pintype "passive"))
      (node (ref "U2") (pin "10") (pinfunction "IO8_10") (pintype "bidirectional"))
    )
    (net (code "15") (name "I2C_PW") (class "Default")
      (node (ref "C1") (pin "1") (pinfunction "1_1") (pintype "passive"))
      (node (ref "C2") (pin "1") (pinfunction "1_1") (pintype "passive"))
      (node (ref "R1-PINH") (pin "2") (pinfunction "2_2") (pintype "passive"))
      (node (ref "R2-PINH") (pin "2") (pinfunction "2_2") (pintype "passive"))
      (node (ref "SENSOR2") (pin "2") (pinfunction "CSB_2") (pintype "input"))
      (node (ref "SENSOR2") (pin "6") (pinfunction "VDDIO_6") (pintype "power_in"))
      (node (ref "SENSOR2") (pin "8") (pinfunction "VDD_8") (pintype "power_in"))
      (node (ref "U2") (pin "17") (pinfunction "IO19_17") (pintype "bidirectional"))
    )
    (net (code "16") (name "INT_RTC") (class "Default")
      (node (ref "R1-PINH1") (pin "1") (pinfunction "1_1") (pintype "passive"))
      (node (ref "TP15") (pin "TP") (pinfunction "TP_TP") (pintype "input"))
      (node (ref "U2") (pin "8") (pinfunction "IO0_8") (pintype "bidirectional"))
      (node (ref "U3") (pin "3") (pinfunction "SQW/~{INT}_3") (pintype "output"))
    )
    (net (code "17") (name "IO{slash}BOOT") (class "Default")
      (node (ref "BOOT_BUTTON") (pin "3") (pinfunction "3_3") (pintype "passive"))
      (node (ref "BOOT_BUTTON") (pin "4") (pinfunction "4_4") (pintype "passive"))
      (node (ref "C6") (pin "1") (pinfunction "1_1") (pintype "passive"))
      (node (ref "R_BOOT") (pin "1") (pinfunction "1_1") (pintype "passive"))
      (node (ref "U2") (pin "15") (pinfunction "IO9_15") (pintype "bidirectional"))
    )
    (net (code "18") (name "IO{slash}CHANGE") (class "Default")
      (node (ref "C10") (pin "1") (pinfunction "1_1") (pintype "passive"))
      (node (ref "CHANGE_BUTTON") (pin "3") (pinfunction "3_3") (pintype "passive"))
      (node (ref "CHANGE_BUTTON") (pin "4") (pinfunction "4_4") (pintype "passive"))
      (node (ref "R_CHANGE") (pin "1") (pinfunction "1_1") (pintype "passive"))
      (node (ref "U2") (pin "23") (pinfunction "IO15_23") (pintype "bidirectional"))
    )
    (net (code "19") (name "MISO") (class "Default")
      (node (ref "D12") (pin "2") (pinfunction "2_2") (pintype "passive"))
      (node (ref "J4") (pin "P7") (pinfunction "DAT0_P7") (pintype "bidirectional"))
      (node (ref "R8") (pin "1") (pinfunction "1_1") (pintype "passive"))
      (node (ref "TP6") (pin "TP") (pinfunction "TP_TP") (pintype "input"))
      (node (ref "U1") (pin "2") (pinfunction "DO(IO1)_2") (pintype "bidirectional"))
      (node (ref "U2") (pin "27") (pinfunction "IO2_27") (pintype "bidirectional"))
    )
    (net (code "20") (name "MOSI") (class "Default")
      (node (ref "D11") (pin "2") (pinfunction "2_2") (pintype "passive"))
      (node (ref "J1") (pin "14") (pinfunction "14_14") (pintype "bidirectional"))
      (node (ref "J4") (pin "P3") (pinfunction "CMD_P3") (pintype "bidirectional"))
      (node (ref "R7") (pin "1") (pinfunction "1_1") (pintype "passive"))
      (node (ref "TP7") (pin "TP") (pinfunction "TP_TP") (pintype "input"))
      (node (ref "U1") (pin "5") (pinfunction "DI(IO0)_5") (pintype "bidirectional"))
      (node (ref "U2") (pin "7") (pinfunction "IO7_7") (pintype "bidirectional"))
    )
    (net (code "21") (name "Net-(D2-CATHODE)") (class "Default")
      (node (ref "C1_BAT1") (pin "1") (pinfunction "1_1") (pintype "passive"))
      (node (ref "D2") (pin "1") (pinfunction "CATHODE_1") (pintype "bidirectional"))
      (node (ref "IC4") (pin "1") (pinfunction "VIN_1") (pintype "bidirectional"))
      (node (ref "IC4") (pin "3") (pinfunction "CE_3") (pintype "bidirectional"))
      (node (ref "Q3") (pin "2") (pinfunction "S_2") (pintype "bidirectional"))
    )
    (net (code "22") (name "Net-(D3-A)") (class "Default")
      (node (ref "C4") (pin "1") (pinfunction "1_1") (pintype "passive"))
      (node (ref "D3") (pin "2") (pinfunction "A_2") (pintype "bidirectional"))
      (node (ref "D4") (pin "1") (pinfunction "K_1") (pintype "bidirectional"))
    )
    (net (code "23") (name "Net-(D7-CATHODE)") (class "Default")
      (node (ref "D7") (pin "1") (pinfunction "CATHODE_1") (pintype "bidirectional"))
      (node (ref "R_CAPACITOR") (pin "1") (pinfunction "1_1") (pintype "passive"))
    )
    (net (code "24") (name "Net-(EPD_C1-Pad2)") (class "Default")
      (node (ref "EPD_C1") (pin "2") (pinfunction "2_2") (pintype "passive"))
      (node (ref "J1") (pin "4") (pinfunction "4_4") (pintype "bidirectional"))
    )
    (net (code "25") (name "Net-(EPD_C2-Pad2)") (class "Default")
      (node (ref "EPD_C2") (pin "2") (pinfunction "2_2") (pintype "passive"))
      (node (ref "J1") (pin "5") (pinfunction "5_5") (pintype "bidirectional"))
    )
    (net (code "26") (name "Net-(EPD_C6-Pad2)") (class "Default")
      (node (ref "EPD_C6") (pin "2") (pinfunction "2_2") (pintype "passive"))
      (node (ref "J1") (pin "18") (pinfunction "18_18") (pintype "bidirectional"))
    )
    (net (code "27") (name "Net-(EPD_C7-Pad2)") (class "Default")
      (node (ref "EPD_C7") (pin "2") (pinfunction "2_2") (pintype "passive"))
      (node (ref "J1") (pin "19") (pinfunction "19_19") (pintype "bidirectional"))
    )
    (net (code "28") (name "Net-(EPD_C8-Pad2)") (class "Default")
      (node (ref "EPD_C8") (pin "2") (pinfunction "2_2") (pintype "passive"))
      (node (ref "J1") (pin "20") (pinfunction "20_20") (pintype "bidirectional"))
    )
    (net (code "29") (name "Net-(EPD_C10-Pad2)") (class "Default")
      (node (ref "EPD_C10") (pin "2") (pinfunction "2_2") (pintype "passive"))
      (node (ref "J1") (pin "22") (pinfunction "22_22") (pintype "bidirectional"))
    )
    (net (code "30") (name "Net-(EPD_C12-Pad2)") (class "Default")
      (node (ref "EPD_C12") (pin "2") (pinfunction "2_2") (pintype "passive"))
      (node (ref "J1") (pin "24") (pinfunction "24_24") (pintype "bidirectional"))
    )
    (net (code "31") (name "Net-(GHC_LED-PadC)") (class "Default")
      (node (ref "GHC_LED") (pin "C") (pinfunction "C_C") (pintype "passive"))
      (node (ref "R1_BAT") (pin "1") (pinfunction "1_1") (pintype "passive"))
    )
    (net (code "32") (name "Net-(IC1-CT)") (class "Default")
      (node (ref "C_DELAY") (pin "1") (pinfunction "1_1") (pintype "passive"))
      (node (ref "IC1") (pin "5") (pinfunction "CT_5") (pintype "bidirectional"))
    )
    (net (code "33") (name "Net-(J2-PadA5)") (class "Default")
      (node (ref "J2") (pin "A5") (pinfunction "A5_A5") (pintype "bidirectional"))
      (node (ref "R2-USB1") (pin "2") (pinfunction "2_2") (pintype "passive"))
    )
    (net (code "34") (name "Net-(J2-PadB5)") (class "Default")
      (node (ref "J2") (pin "B5") (pinfunction "B5_B5") (pintype "bidirectional"))
      (node (ref "R2-USB") (pin "1") (pinfunction "1_1") (pintype "passive"))
    )
    (net (code "35") (name "Net-(U-PROG)") (class "Default")
      (node (ref "R2_BAT") (pin "2") (pinfunction "2_2") (pintype "passive"))
      (node (ref "U") (pin "5") (pinfunction "PROG_5") (pintype "input"))
    )
    (net (code "36") (name "Net-(U-STAT)") (class "Default")
      (node (ref "R1_BAT") (pin "2") (pinfunction "2_2") (pintype "passive"))
      (node (ref "U") (pin "1") (pinfunction "STAT_1") (pintype "output"))
    )
    (net (code "37") (name "PREVGH") (class "Default")
      (node (ref "D5") (pin "1") (pinfunction "K_1") (pintype "bidirectional"))
      (node (ref "EPD_C9") (pin "2") (pinfunction "2_2") (pintype "passive"))
      (node (ref "J1") (pin "21") (pinfunction "21_21") (pintype "bidirectional"))
    )
    (net (code "38") (name "PREVGL") (class "Default")
      (node (ref "D4") (pin "2") (pinfunction "A_2") (pintype "bidirectional"))
      (node (ref "EPD_C11") (pin "2") (pinfunction "2_2") (pintype "passive"))
      (node (ref "J1") (pin "23") (pinfunction "23_23") (pintype "bidirectional"))
    )
    (net (code "39") (name "RESE") (class "Default")
      (node (ref "J1") (pin "3") (pinfunction "3_3") (pintype "bidirectional"))
      (node (ref "Q1") (pin "2") (pinfunction "S_2") (pintype "bidirectional"))
      (node (ref "R3") (pin "2") (pinfunction "2_2") (pintype "passive"))
      (node (ref "SJ1") (pin "2") (pinfunction "2_2") (pintype "passive"))
    )
    (net (code "40") (name "RESE'") (class "Default")
      (node (ref "R2") (pin "2") (pinfunction "2_2") (pintype "passive"))
      (node (ref "R3") (pin "1") (pinfunction "1_1") (pintype "passive"))
    )
    (net (code "41") (name "RESET") (class "Default")
      (node (ref "C5") (pin "1") (pinfunction "1_1") (pintype "passive"))
      (node (ref "IC1") (pin "1") (pinfunction "VOUT_1") (pintype "bidirectional"))
      (node (ref "RESET_BUTTON") (pin "3") (pinfunction "3_3") (pintype "passive"))
      (node (ref "RESET_BUTTON") (pin "4") (pinfunction "4_4") (pintype "passive"))
      (node (ref "R_RESET") (pin "1") (pinfunction "1_1") (pintype "passive"))
      (node (ref "U2") (pin "3") (pinfunction "EN_3") (pintype "input"))
    )
    (net (code "42") (name "RTC_RST") (class "Default")
      (node (ref "U2") (pin "16") (pinfunction "IO18_16") (pintype "bidirectional"))
      (node (ref "U3") (pin "4") (pinfunction "~{RST}_4") (pintype "input"))
    )
    (net (code "43") (name "RX") (class "Default")
      (node (ref "TP2") (pin "TP") (pinfunction "TP_TP") (pintype "input"))
      (node (ref "U2") (pin "24") (pinfunction "RXD0/GPIO17_24") (pintype "bidirectional"))
    )
    (net (code "44") (name "SCK") (class "Default")
      (node (ref "D10") (pin "2") (pinfunction "2_2") (pintype "passive"))
      (node (ref "J1") (pin "13") (pinfunction "13_13") (pintype "bidirectional"))
      (node (ref "J4") (pin "P5") (pinfunction "CLK_P5") (pintype "bidirectional"))
      (node (ref "R6") (pin "1") (pinfunction "1_1") (pintype "passive"))
      (node (ref "TP8") (pin "TP") (pinfunction "TP_TP") (pintype "input"))
      (node (ref "U1") (pin "6") (pinfunction "CLK_6") (pintype "input"))
      (node (ref "U2") (pin "6") (pinfunction "IO6_6") (pintype "bidirectional"))
    )
    (net (code "45") (name "SCL") (class "Default")
      (node (ref "J3") (pin "4") (pinfunction "4_4") (pintype "passive"))
      (node (ref "R2-PINH") (pin "1") (pinfunction "1_1") (pintype "passive"))
      (node (ref "SENSOR2") (pin "4") (pinfunction "SCK_4") (pintype "input"))
      (node (ref "U2") (pin "20") (pinfunction "IO22_20") (pintype "bidirectional"))
      (node (ref "U3") (pin "16") (pinfunction "SCL_16") (pintype "input"))
      (node (ref "U4") (pin "7") (pinfunction "SCL_7") (pintype "input"))
    )
    (net (code "46") (name "SDA") (class "Default")
      (node (ref "J3") (pin "3") (pinfunction "3_3") (pintype "passive"))
      (node (ref "R1-PINH") (pin "1") (pinfunction "1_1") (pintype "passive"))
      (node (ref "SENSOR2") (pin "3") (pinfunction "SDI_3") (pintype "bidirectional"))
      (node (ref "U2") (pin "19") (pinfunction "IO21_19") (pintype "bidirectional"))
      (node (ref "U3") (pin "15") (pinfunction "SDA_15") (pintype "bidirectional"))
      (node (ref "U4") (pin "8") (pinfunction "SDA_8") (pintype "bidirectional"))
    )
    (net (code "47") (name "SRC") (class "Default")
      (node (ref "C4") (pin "2") (pinfunction "2_2") (pintype "passive"))
      (node (ref "D5") (pin "2") (pinfunction "A_2") (pintype "bidirectional"))
      (node (ref "L1") (pin "1") (pinfunction "1_1") (pintype "passive"))
      (node (ref "Q1") (pin "3") (pinfunction "D_3") (pintype "bidirectional"))
    )
    (net (code "48") (name "SS_SD") (class "Default")
      (node (ref "D8") (pin "2") (pinfunction "2_2") (pintype "passive"))
      (node (ref "J4") (pin "P2") (pinfunction "CD/DAT3_P2") (pintype "bidirectional"))
      (node (ref "R10") (pin "1") (pinfunction "1_1") (pintype "passive"))
      (node (ref "U2") (pin "4") (pinfunction "IO4_4") (pintype "bidirectional"))
    )
    (net (code "49") (name "TX") (class "Default")
      (node (ref "TP1") (pin "TP") (pinfunction "TP_TP") (pintype "input"))
      (node (ref "U2") (pin "25") (pinfunction "TXD0/GPIO16_25") (pintype "bidirectional"))
    )
    (net (code "50") (name "USB_D+") (class "Default")
      (node (ref "D1") (pin "1") (pinfunction "I/O1_1_1") (pintype "bidirectional"))
      (node (ref "U2") (pin "14") (pinfunction "IO13_14") (pintype "bidirectional"))
    )
    (net (code "51") (name "USB_D-") (class "Default")
      (node (ref "D1") (pin "3") (pinfunction "I/O2_1_3") (pintype "bidirectional"))
      (node (ref "U2") (pin "13") (pinfunction "IO12_13") (pintype "bidirectional"))
    )
    (net (code "52") (name "VBAT") (class "Default")
      (node (ref "C2_BAT") (pin "1") (pinfunction "1_1") (pintype "passive"))
      (node (ref "Q3") (pin "3") (pinfunction "D_3") (pintype "bidirectional"))
      (node (ref "TP3") (pin "TP") (pinfunction "TP_TP") (pintype "input"))
      (node (ref "U") (pin "3") (pinfunction "VBAT_3") (pintype "power_in"))
      (node (ref "U4") (pin "2") (pinfunction "CELL_2") (pintype "power_in"))
      (node (ref "U4") (pin "3") (pinfunction "VDD_3") (pintype "power_in"))
    )
    (net (code "53") (name "VBUS") (class "Default")
      (node (ref "C1_BAT") (pin "1") (pinfunction "1_1") (pintype "passive"))
      (node (ref "C4_USB") (pin "1") (pinfunction "1_1") (pintype "passive"))
      (node (ref "C5_USB") (pin "1") (pinfunction "1_1") (pintype "passive"))
      (node (ref "D1") (pin "5") (pinfunction "VBUS_5") (pintype "bidirectional"))
      (node (ref "D2") (pin "2") (pinfunction "ANODE_2") (pintype "bidirectional"))
      (node (ref "GHC_LED") (pin "A") (pinfunction "A_A") (pintype "passive"))
      (node (ref "PFMF.050.1") (pin "2") (pinfunction "2_2") (pintype "passive"))
      (node (ref "Q3") (pin "1") (pinfunction "G_1") (pintype "bidirectional"))
      (node (ref "R1_PWRUSB") (pin "2") (pinfunction "2_2") (pintype "passive"))
      (node (ref "TP14") (pin "TP") (pinfunction "TP_TP") (pintype "input"))
      (node (ref "U") (pin "4") (pinfunction "VIN_4") (pintype "power_in"))
    )
    (net (code "54") (name "VRTC") (class "Default")
      (node (ref "C10_SUPERCAP") (pin "2") (pinfunction "2_2") (pintype "passive"))
      (node (ref "C8") (pin "1") (pinfunction "1_1") (pintype "passive"))
      (node (ref "R_CAPACITOR") (pin "2") (pinfunction "2_2") (pintype "passive"))
      (node (ref "U3") (pin "14") (pinfunction "VBAT_14") (pintype "power_in"))
    )
    (net (code "55") (name "VUSB") (class "Default")
      (node (ref "J2") (pin "A4") (pinfunction "A4_A4") (pintype "bidirectional"))
      (node (ref "J2") (pin "A9") (pinfunction "A9_A9") (pintype "bidirectional"))
      (node (ref "J2") (pin "B4") (pinfunction "B4_B4") (pintype "bidirectional"))
      (node (ref "J2") (pin "B9") (pinfunction "B9_B9") (pintype "bidirectional"))
      (node (ref "PFMF.050.1") (pin "1") (pinfunction "1_1") (pintype "passive"))
    )
    (net (code "56") (name "unconnected-(IC1-NC-Pad4)") (class "Default")
      (node (ref "IC1") (pin "4") (pinfunction "NC_4") (pintype "no_connect"))
    )
    (net (code "57") (name "unconnected-(IC4-NC-Pad4)") (class "Default")
      (node (ref "IC4") (pin "4") (pinfunction "NC_4") (pintype "no_connect"))
    )
    (net (code "58") (name "unconnected-(J1-Pad1)") (class "Default")
      (node (ref "J1") (pin "1") (pinfunction "1_1") (pintype "bidirectional"))
    )
    (net (code "59") (name "unconnected-(J1-Pad6)") (class "Default")
      (node (ref "J1") (pin "6") (pinfunction "6_6") (pintype "bidirectional"))
    )
    (net (code "60") (name "unconnected-(J1-Pad7)") (class "Default")
      (node (ref "J1") (pin "7") (pinfunction "7_7") (pintype "bidirectional"))
    )
    (net (code "61") (name "unconnected-(J2-PadA8)") (class "Default")
      (node (ref "J2") (pin "A8") (pinfunction "A8_A8") (pintype "bidirectional"))
    )
    (net (code "62") (name "unconnected-(J2-PadB8)") (class "Default")
      (node (ref "J2") (pin "B8") (pinfunction "B8_B8") (pintype "bidirectional"))
    )
    (net (code "63") (name "unconnected-(J4-DAT1-PadP8)") (class "Default")
      (node (ref "J4") (pin "P8") (pinfunction "DAT1_P8") (pintype "bidirectional"))
    )
    (net (code "64") (name "unconnected-(J4-DAT2-PadP1)") (class "Default")
      (node (ref "J4") (pin "P1") (pinfunction "DAT2_P1") (pintype "bidirectional"))
    )
    (net (code "65") (name "unconnected-(J4-DETECTION_1-PadS1)") (class "Default")
      (node (ref "J4") (pin "S1") (pinfunction "DETECTION_1_S1") (pintype "bidirectional"))
    )
    (net (code "66") (name "unconnected-(J4-DETECTION_2-PadS2)") (class "Default")
      (node (ref "J4") (pin "S2") (pinfunction "DETECTION_2_S2") (pintype "bidirectional"))
    )
    (net (code "67") (name "unconnected-(U2-NC-Pad22)") (class "Default")
      (node (ref "U2") (pin "22") (pinfunction "NC_22") (pintype "no_connect"))
    )
    (net (code "68") (name "unconnected-(U4-~{ALERT}-Pad5)") (class "Default")
      (node (ref "U4") (pin "5") (pinfunction "~{ALERT}_5") (pintype "output"))
    )
  )
)
